# SCH_Power_Distribution_Board_2022-02-23.net
KiCad netlist of a schematic drawn in EasyEDA
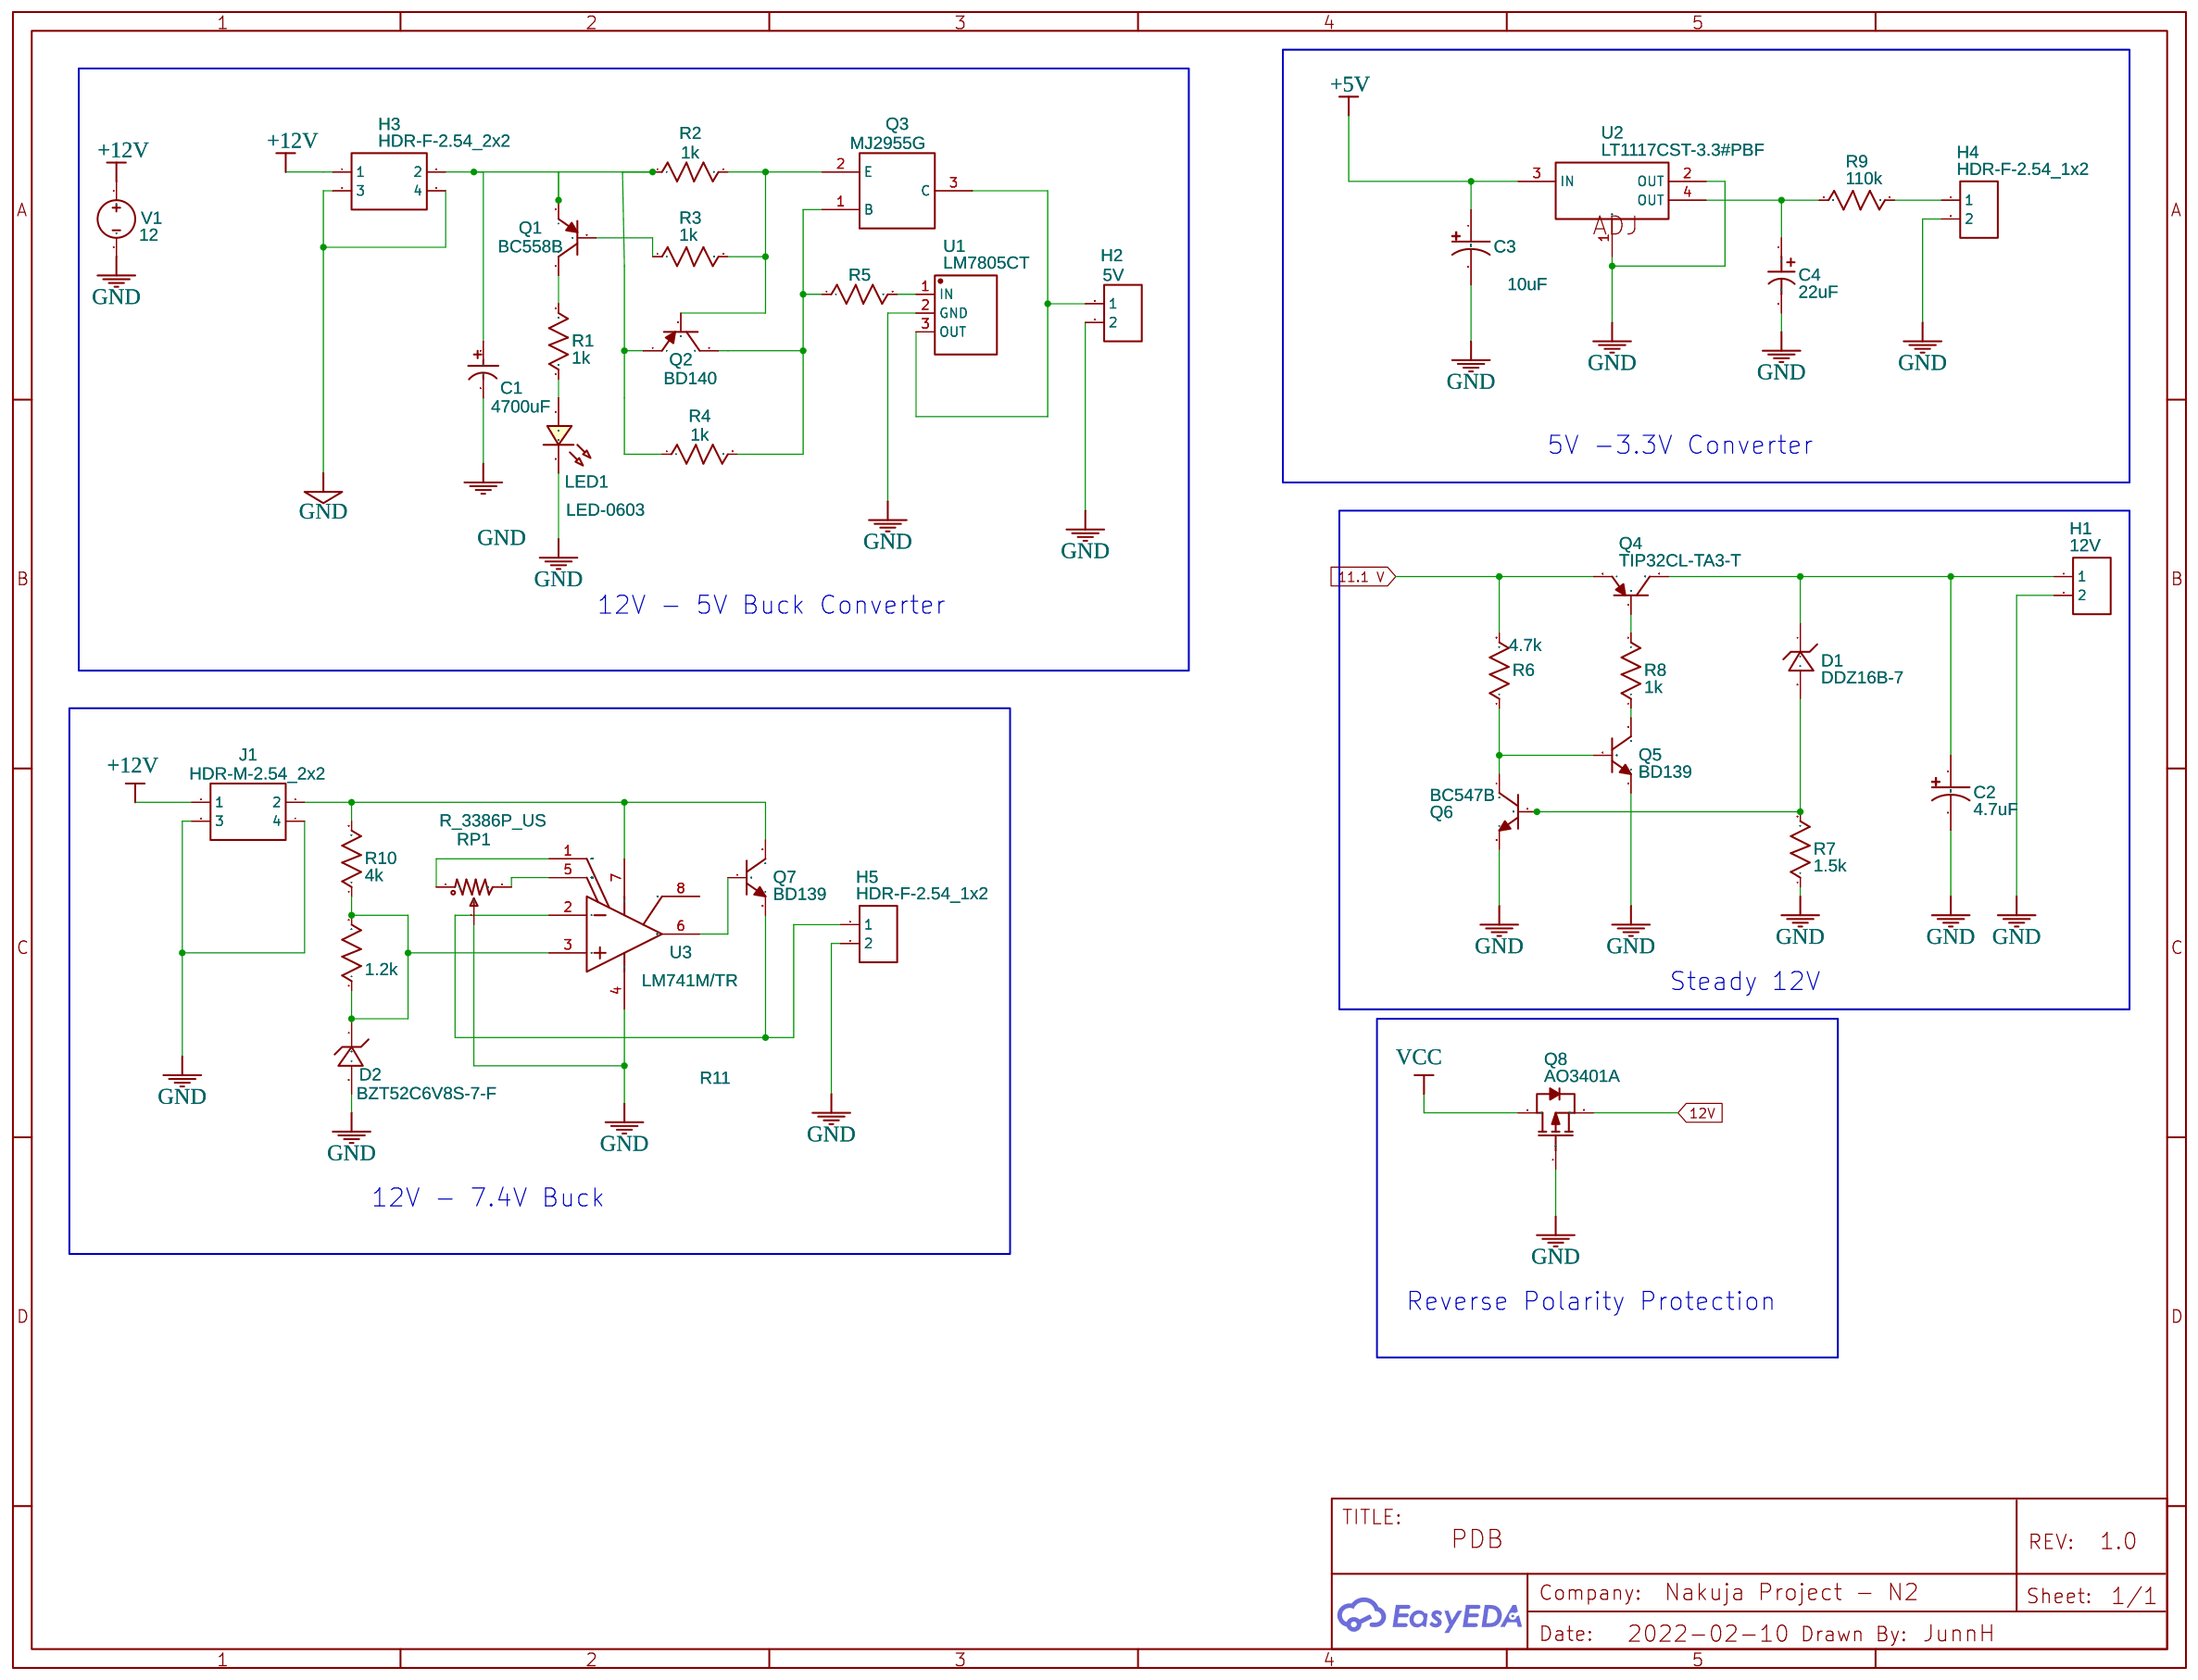
[diagram p0: schematic sheet]

(export (version "E")
  (design (tool "Eeschema 10.0.6"))
  (components
    (comp (ref "C1")
      (value "4700uF")
      (fields
        (field (name "BOM_Manufacturer Part") "4700uF 25V 16*25V")
        (field (name "BOM_Supplier Part") "C45070")
      )
      (libsource (lib "") (part "4700uF 25V 16*25V"))
    )
    (comp (ref "C2")
      (value "4.7uF")
      (fields
        (field (name "BOM_Manufacturer Part") "EEEHP1E4R7R")
        (field (name "BOM_Supplier Part") "C401861")
      )
      (libsource (lib "") (part "EEEHP1E4R7R"))
    )
    (comp (ref "C3")
      (value "10uF")
      (fields
        (field (name "BOM_Manufacturer Part") "VE-100M1H0505-TRO")
        (field (name "BOM_Supplier Part") "C249452")
      )
      (libsource (lib "") (part "VE-100M1H0505-TRO"))
    )
    (comp (ref "C4")
      (value "22uF")
      (fields
        (field (name "BOM_Manufacturer Part") "RVT22UF50V67RV0028")
        (field (name "BOM_Supplier Part") "C2836438")
      )
      (libsource (lib "") (part "RVT22UF50V67RV0028"))
    )
    (comp (ref "D1")
      (value "DDZ16B-7")
      (fields (field (name "BOM_Supplier Part") "C459533"))
      (libsource (lib "") (part "DDZ16B-7"))
    )
    (comp (ref "D2")
      (value "BZT52C6V8S-7-F")
      (fields (field (name "BOM_Supplier Part") "C124211"))
      (libsource (lib "") (part "BZT52C6V8S-7-F"))
    )
    (comp (ref "H1")
      (value "12V")
      (fields (field (name "BOM_Supplier Part") "C49661"))
      (libsource (lib "") (part "HDR-F-2.54_1x2"))
    )
    (comp (ref "H2")
      (value "5V")
      (fields (field (name "BOM_Supplier Part") "C49661"))
      (libsource (lib "") (part "HDR-F-2.54_1x2"))
    )
    (comp (ref "H3")
      (value "HDR-F-2.54_2x2")
      (fields (field (name "BOM_Supplier Part") "C239342"))
      (libsource (lib "") (part "HDR-F-2.54_2x2"))
    )
    (comp (ref "H4")
      (value "HDR-F-2.54_1x2")
      (fields (field (name "BOM_Supplier Part") "C49661"))
      (libsource (lib "") (part "HDR-F-2.54_1x2"))
    )
    (comp (ref "H5")
      (value "HDR-F-2.54_1x2")
      (fields (field (name "BOM_Supplier Part") "C49661"))
      (libsource (lib "") (part "HDR-F-2.54_1x2"))
    )
    (comp (ref "J1")
      (value "HDR-M-2.54_2x2")
      (fields (field (name "BOM_Supplier Part") "C66690"))
      (libsource (lib "") (part "HDR-M-2.54_2x2"))
    )
    (comp (ref "LED1")
      (value "LED-0603")
      (fields
        (field (name "BOM_Manufacturer Part") "19-217/R6C-AL1M2VY/3T")
        (field (name "BOM_Supplier Part") "C72044")
      )
      (libsource (lib "") (part "LED-0603_R"))
    )
    (comp (ref "Q1")
      (value "BC558B")
      (fields (field (name "BOM_Supplier Part") "C713619"))
      (libsource (lib "") (part "BC558B"))
    )
    (comp (ref "Q2")
      (value "BD140")
      (fields
        (field (name "BOM_Manufacturer Part") "BD14016STU")
        (field (name "BOM_Supplier Part") "C900680")
      )
      (libsource (lib "") (part "BD14016STU"))
    )
    (comp (ref "Q3")
      (value "MJ2955G")
      (fields (field (name "BOM_Supplier Part") "C223588"))
      (libsource (lib "") (part "MJ2955G"))
    )
    (comp (ref "Q4")
      (value "TIP32CL-TA3-T")
      (fields (field (name "BOM_Supplier Part") "C127015"))
      (libsource (lib "") (part "TIP32CL-TA3-T"))
    )
    (comp (ref "Q5")
      (value "BD139")
      (fields
        (field (name "BOM_Manufacturer Part") "BD13916STU")
        (field (name "BOM_Supplier Part") "C900678")
      )
      (libsource (lib "") (part "BD13916STU"))
    )
    (comp (ref "Q6")
      (value "BC547B")
      (fields (field (name "BOM_Supplier Part") "C713613"))
      (libsource (lib "") (part "BC547B"))
    )
    (comp (ref "Q7")
      (value "BD139")
      (fields (field (name "BOM_Supplier Part") "C27866"))
      (libsource (lib "") (part "BD139"))
    )
    (comp (ref "Q8")
      (value "AO3401A")
      (fields (field (name "BOM_Supplier Part") "C15127"))
      (libsource (lib "") (part "AO3401A"))
    )
    (comp (ref "R1") (value "1k") (libsource (lib "") (part "R_0603_US_1")))
    (comp (ref "R2") (value "1k") (libsource (lib "") (part "R_0603_US")))
    (comp (ref "R3") (value "1k") (libsource (lib "") (part "R_0603_US")))
    (comp (ref "R4") (value "1k") (libsource (lib "") (part "R_0603_US")))
    (comp (ref "R5") (value "1k") (libsource (lib "") (part "R_0603_US")))
    (comp (ref "R6") (value "4.7k") (libsource (lib "") (part "R_0603_US_1")))
    (comp (ref "R7") (value "1.5k") (libsource (lib "") (part "R_0603_US_1")))
    (comp (ref "R8") (value "1k") (libsource (lib "") (part "R_0603_US_1")))
    (comp (ref "R9") (value "110k") (libsource (lib "") (part "R_0603_US")))
    (comp (ref "R10") (value "4k") (libsource (lib "") (part "R_0603_US_1")))
    (comp (ref "R11") (value "1.2k") (libsource (lib "") (part "R_0603_US_1")))
    (comp (ref "RP1") (value "R_3386P_US") (libsource (lib "") (part "R_3386P_US")))
    (comp (ref "U1")
      (value "LM7805CT")
      (fields (field (name "BOM_Supplier Part") "C22146"))
      (libsource (lib "") (part "LM7805CT"))
    )
    (comp (ref "U2")
      (value "LT1117CST-3.3#PBF")
      (fields (field (name "BOM_Supplier Part") "C140395"))
      (libsource (lib "") (part "LT1117CST-3.3#PBF"))
    )
    (comp (ref "U3")
      (value "LM741M/TR")
      (fields (field (name "BOM_Supplier Part") "C356704"))
      (libsource (lib "") (part "LM741M/TR"))
    )
    (comp (ref "V1") (value "12") (libsource (lib "") (part "VDC")))
  )
  (nets
    (net (code "1") (name "+5V") (class "Default")
      (node (ref "C3") (pin "1") (pinfunction "1_1") (pintype "unspecified"))
      (node (ref "U2") (pin "3") (pinfunction "IN_3") (pintype "passive"))
    )
    (net (code "2") (name "+12V") (class "Default")
      (node (ref "H3") (pin "1") (pinfunction "1_1") (pintype "unspecified"))
      (node (ref "J1") (pin "1") (pinfunction "1_1") (pintype "input"))
      (node (ref "V1") (pin "1") (pinfunction "1_1") (pintype "unspecified"))
    )
    (net (code "3") (name "11.1 V") (class "Default")
      (node (ref "Q4") (pin "3") (pinfunction "E_3") (pintype "unspecified"))
      (node (ref "R6") (pin "2") (pinfunction "2_2") (pintype "unspecified"))
    )
    (net (code "4") (name "12V") (class "Default")
      (node (ref "Q8") (pin "2") (pinfunction "S_2") (pintype "unspecified"))
    )
    (net (code "5") (name "GND") (class "Default")
      (node (ref "C1") (pin "2") (pinfunction "2_2") (pintype "input"))
      (node (ref "C2") (pin "2") (pinfunction "2_2") (pintype "unspecified"))
      (node (ref "C3") (pin "2") (pinfunction "2_2") (pintype "unspecified"))
      (node (ref "C4") (pin "2") (pinfunction "2_2") (pintype "input"))
      (node (ref "D2") (pin "2") (pinfunction "A_2") (pintype "unspecified"))
      (node (ref "H1") (pin "2") (pinfunction "2_2") (pintype "input"))
      (node (ref "H2") (pin "2") (pinfunction "2_2") (pintype "input"))
      (node (ref "H3") (pin "3") (pinfunction "3_3") (pintype "unspecified"))
      (node (ref "H3") (pin "4") (pinfunction "4_4") (pintype "unspecified"))
      (node (ref "H4") (pin "2") (pinfunction "2_2") (pintype "input"))
      (node (ref "H5") (pin "2") (pinfunction "2_2") (pintype "input"))
      (node (ref "J1") (pin "3") (pinfunction "3_3") (pintype "input"))
      (node (ref "J1") (pin "4") (pinfunction "4_4") (pintype "input"))
      (node (ref "LED1") (pin "2") (pinfunction "2_2") (pintype "unspecified"))
      (node (ref "Q5") (pin "1") (pinfunction "E_1") (pintype "unspecified"))
      (node (ref "Q6") (pin "3") (pinfunction "E_3") (pintype "input"))
      (node (ref "Q8") (pin "1") (pinfunction "G_1") (pintype "unspecified"))
      (node (ref "R7") (pin "1") (pinfunction "1_1") (pintype "unspecified"))
      (node (ref "RP1") (pin "2") (pinfunction "2_2") (pintype "unspecified"))
      (node (ref "U1") (pin "2") (pinfunction "GND_2") (pintype "unspecified"))
      (node (ref "U2") (pin "1") (pinfunction "ADJ_1") (pintype "passive"))
      (node (ref "U2") (pin "2") (pinfunction "OUT_2") (pintype "passive"))
      (node (ref "U3") (pin "4") (pinfunction "V-_4") (pintype "passive"))
      (node (ref "V1") (pin "2") (pinfunction "2_2") (pintype "unspecified"))
    )
    (net (code "6") (name "Net-(C4-Pad1)") (class "Default")
      (node (ref "C4") (pin "1") (pinfunction "1_1") (pintype "input"))
      (node (ref "R9") (pin "1") (pinfunction "1_1") (pintype "unspecified"))
      (node (ref "U2") (pin "4") (pinfunction "OUT_4") (pintype "passive"))
    )
    (net (code "7") (name "Net-(D2-C)") (class "Default")
      (node (ref "D2") (pin "1") (pinfunction "C_1") (pintype "unspecified"))
      (node (ref "R10") (pin "1") (pinfunction "1_1") (pintype "unspecified"))
      (node (ref "R11") (pin "1") (pinfunction "1_1") (pintype "unspecified"))
      (node (ref "R11") (pin "2") (pinfunction "2_2") (pintype "unspecified"))
      (node (ref "U3") (pin "3") (pinfunction "IN+_3") (pintype "unspecified"))
    )
    (net (code "8") (name "Net-(H4-Pad1)") (class "Default")
      (node (ref "H4") (pin "1") (pinfunction "1_1") (pintype "input"))
      (node (ref "R9") (pin "2") (pinfunction "2_2") (pintype "unspecified"))
    )
    (net (code "9") (name "Net-(LED1-Pad1)") (class "Default")
      (node (ref "LED1") (pin "1") (pinfunction "1_1") (pintype "unspecified"))
      (node (ref "R1") (pin "1") (pinfunction "1_1") (pintype "unspecified"))
    )
    (net (code "10") (name "Net-(Q1-B)") (class "Default")
      (node (ref "Q1") (pin "2") (pinfunction "B_2") (pintype "input"))
      (node (ref "R3") (pin "1") (pinfunction "1_1") (pintype "unspecified"))
    )
    (net (code "11") (name "Net-(Q1-C)") (class "Default")
      (node (ref "Q1") (pin "1") (pinfunction "C_1") (pintype "input"))
      (node (ref "R1") (pin "2") (pinfunction "2_2") (pintype "unspecified"))
    )
    (net (code "12") (name "Net-(Q1-E)") (class "Default")
      (node (ref "C1") (pin "1") (pinfunction "1_1") (pintype "input"))
      (node (ref "H3") (pin "2") (pinfunction "2_2") (pintype "unspecified"))
      (node (ref "Q1") (pin "3") (pinfunction "E_3") (pintype "input"))
      (node (ref "Q2") (pin "1") (pinfunction "E_1") (pintype "input"))
      (node (ref "R2") (pin "1") (pinfunction "1_1") (pintype "unspecified"))
      (node (ref "R4") (pin "1") (pinfunction "1_1") (pintype "unspecified"))
    )
    (net (code "13") (name "Net-(Q2-B)") (class "Default")
      (node (ref "Q2") (pin "3") (pinfunction "B_3") (pintype "input"))
      (node (ref "Q3") (pin "2") (pinfunction "E_2") (pintype "unspecified"))
      (node (ref "R2") (pin "2") (pinfunction "2_2") (pintype "unspecified"))
      (node (ref "R3") (pin "2") (pinfunction "2_2") (pintype "unspecified"))
    )
    (net (code "14") (name "Net-(Q2-C)") (class "Default")
      (node (ref "Q2") (pin "2") (pinfunction "C_2") (pintype "input"))
      (node (ref "Q3") (pin "1") (pinfunction "B_1") (pintype "unspecified"))
      (node (ref "R4") (pin "2") (pinfunction "2_2") (pintype "unspecified"))
      (node (ref "R5") (pin "1") (pinfunction "1_1") (pintype "unspecified"))
    )
    (net (code "15") (name "Net-(Q3-C)") (class "Default")
      (node (ref "H2") (pin "1") (pinfunction "1_1") (pintype "input"))
      (node (ref "Q3") (pin "3") (pinfunction "C_3") (pintype "unspecified"))
      (node (ref "U1") (pin "3") (pinfunction "OUT_3") (pintype "unspecified"))
    )
    (net (code "16") (name "Net-(Q4-B)") (class "Default")
      (node (ref "Q4") (pin "1") (pinfunction "B_1") (pintype "unspecified"))
      (node (ref "R8") (pin "2") (pinfunction "2_2") (pintype "unspecified"))
    )
    (net (code "17") (name "Net-(Q4-C)") (class "Default")
      (node (ref "C2") (pin "1") (pinfunction "1_1") (pintype "unspecified"))
      (node (ref "D1") (pin "1") (pinfunction "1_1") (pintype "unspecified"))
      (node (ref "H1") (pin "1") (pinfunction "1_1") (pintype "input"))
      (node (ref "Q4") (pin "2") (pinfunction "C_2") (pintype "unspecified"))
    )
    (net (code "18") (name "Net-(Q5-B)") (class "Default")
      (node (ref "Q5") (pin "3") (pinfunction "B_3") (pintype "unspecified"))
      (node (ref "Q6") (pin "1") (pinfunction "C_1") (pintype "input"))
      (node (ref "R6") (pin "1") (pinfunction "1_1") (pintype "unspecified"))
    )
    (net (code "19") (name "Net-(Q5-C)") (class "Default")
      (node (ref "Q5") (pin "2") (pinfunction "C_2") (pintype "unspecified"))
      (node (ref "R8") (pin "1") (pinfunction "1_1") (pintype "unspecified"))
    )
    (net (code "20") (name "Net-(Q6-B)") (class "Default")
      (node (ref "D1") (pin "2") (pinfunction "2_2") (pintype "unspecified"))
      (node (ref "Q6") (pin "2") (pinfunction "B_2") (pintype "input"))
      (node (ref "R7") (pin "2") (pinfunction "2_2") (pintype "unspecified"))
    )
    (net (code "21") (name "Net-(Q7-B)") (class "Default")
      (node (ref "Q7") (pin "1") (pinfunction "B_1") (pintype "unspecified"))
      (node (ref "U3") (pin "6") (pinfunction "OUT_6") (pintype "output"))
    )
    (net (code "22") (name "Net-(Q7-C)") (class "Default")
      (node (ref "J1") (pin "2") (pinfunction "2_2") (pintype "input"))
      (node (ref "Q7") (pin "2") (pinfunction "C_2") (pintype "unspecified"))
      (node (ref "R10") (pin "2") (pinfunction "2_2") (pintype "unspecified"))
      (node (ref "U3") (pin "7") (pinfunction "V+_7") (pintype "passive"))
    )
    (net (code "23") (name "Net-(Q7-E)") (class "Default")
      (node (ref "H5") (pin "1") (pinfunction "1_1") (pintype "input"))
      (node (ref "Q7") (pin "3") (pinfunction "E_3") (pintype "unspecified"))
      (node (ref "U3") (pin "2") (pinfunction "IN-_2") (pintype "unspecified"))
    )
    (net (code "24") (name "Net-(RP1-Pad1)") (class "Default")
      (node (ref "RP1") (pin "1") (pinfunction "1_1") (pintype "unspecified"))
      (node (ref "U3") (pin "1") (pinfunction "OFFSET_NULL_1") (pintype "unspecified"))
    )
    (net (code "25") (name "Net-(RP1-Pad3)") (class "Default")
      (node (ref "RP1") (pin "3") (pinfunction "3_3") (pintype "unspecified"))
      (node (ref "U3") (pin "5") (pinfunction "OFFSET_NULL_5") (pintype "unspecified"))
    )
    (net (code "26") (name "Net-(U1-IN)") (class "Default")
      (node (ref "R5") (pin "2") (pinfunction "2_2") (pintype "unspecified"))
      (node (ref "U1") (pin "1") (pinfunction "IN_1") (pintype "unspecified"))
    )
    (net (code "27") (name "VCC") (class "Default")
      (node (ref "Q8") (pin "3") (pinfunction "D_3") (pintype "unspecified"))
    )
    (net (code "28") (name "unconnected-(U3-NC-Pad8)") (class "Default")
      (node (ref "U3") (pin "8") (pinfunction "NC_8") (pintype "unspecified"))
    )
  )
)
